# EndEffector.net
KiCad netlist of a schematic drawn in EAGLE
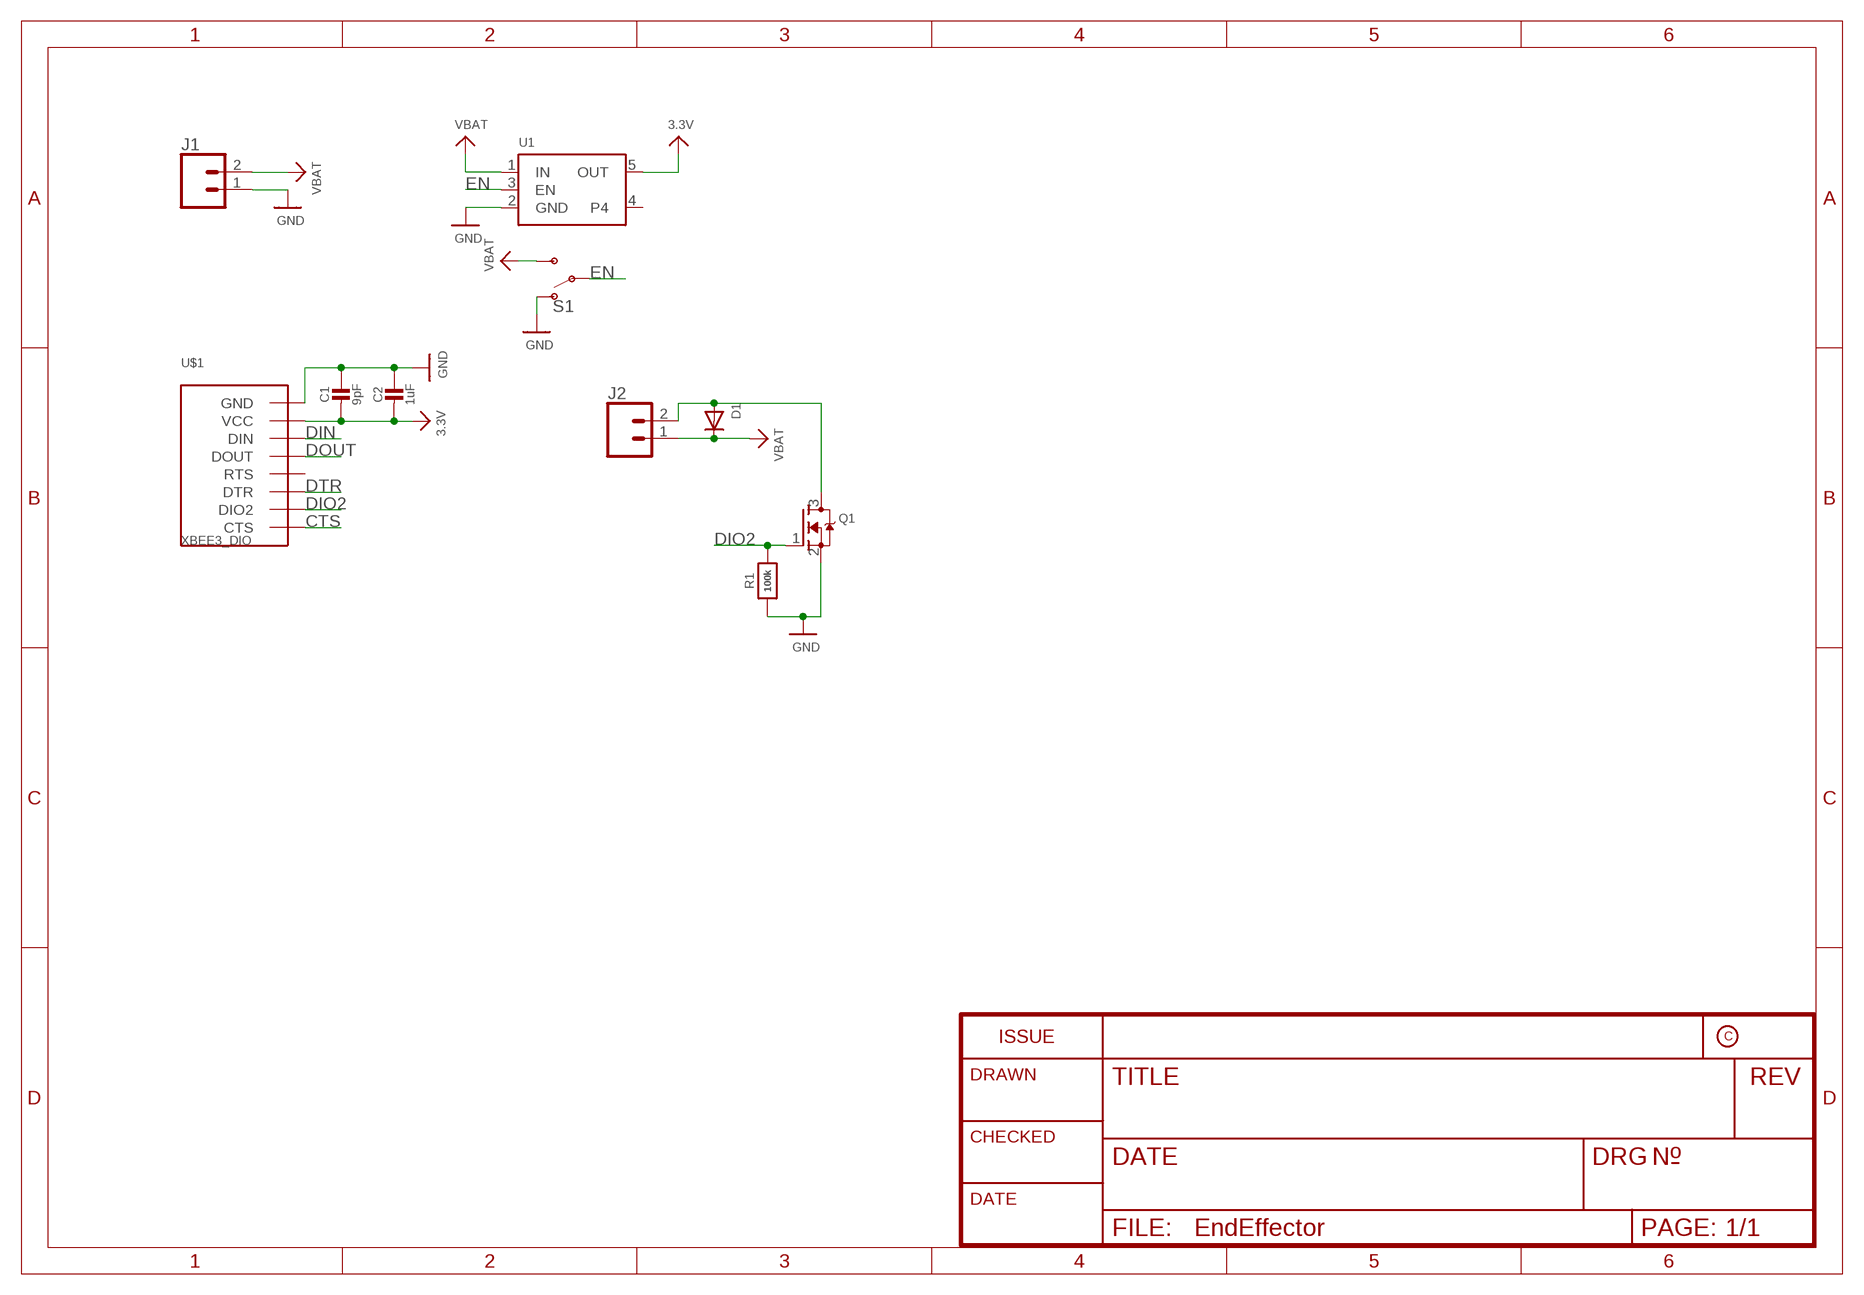
[diagram p0: schematic, sheet 1]

(export (version "E")
  (design (tool "Eeschema 10.0.6"))
  (components
    (comp (ref "C1")
      (value "9pF")
      (footprint "eagle-import:_0603")
      (libsource (lib "eagle-import") (part "CAP_CERAMIC_0603"))
    )
    (comp (ref "C2")
      (value "1uF")
      (footprint "eagle-import:_0603")
      (libsource (lib "eagle-import") (part "CAP_CERAMIC_0603"))
    )
    (comp (ref "D1")
      (value "DIODESOD-123")
      (footprint "eagle-import:SOD-123")
      (libsource (lib "eagle-import") (part "DIODESOD-123"))
    )
    (comp (ref "J1")
      (value "CONN_02")
      (footprint "eagle-import:1X02")
      (libsource (lib "eagle-import") (part "CONN_02"))
    )
    (comp (ref "J2")
      (value "CONN_02")
      (footprint "eagle-import:1X02")
      (libsource (lib "eagle-import") (part "CONN_02"))
    )
    (comp (ref "Q1")
      (value "MOSFET-NREFLOW")
      (footprint "eagle-import:SOT23")
      (libsource (lib "eagle-import") (part "MOSFET-NREFLOW"))
    )
    (comp (ref "R1")
      (value "100k")
      (footprint "eagle-import:_0603")
      (libsource (lib "eagle-import") (part "RESISTOR_0603"))
    )
    (comp (ref "S1")
      (value "SWITCH-SPDT-SMD-RIGHT-ANGLE")
      (footprint "eagle-import:SWITCH_SPST_SMD_A")
      (libsource (lib "eagle-import") (part "SWITCH-SPDT-SMD-RIGHT-ANGLE"))
    )
    (comp (ref "U$1")
      (value "XBEE3_DIO")
      (footprint "eagle-import:XBEE3_MICRO")
      (libsource (lib "eagle-import") (part "XBEE3_DIO"))
    )
    (comp (ref "U1")
      (value "VREG_SOT23-5")
      (footprint "eagle-import:SOT23-5")
      (libsource (lib "eagle-import") (part "VREG_SOT23-5"))
    )
  )
  (nets
    (net (code "1") (name "/CTS") (class "Default")
      (node (ref "U$1") (pin "CTS/DIO7") (pinfunction "CTS_CTS/DIO7") (pintype "bidirectional"))
    )
    (net (code "2") (name "/DIN") (class "Default")
      (node (ref "U$1") (pin "DIN/CONFIG/DIO14") (pinfunction "DIN_DIN/CONFIG/DIO14") (pintype "bidirectional"))
    )
    (net (code "3") (name "/DIO2") (class "Default")
      (node (ref "Q1") (pin "1") (pinfunction "G_1") (pintype "bidirectional"))
      (node (ref "R1") (pin "2") (pinfunction "2_2") (pintype "passive"))
      (node (ref "U$1") (pin "AD2/DIO2") (pinfunction "DIO2_AD2/DIO2") (pintype "bidirectional"))
    )
    (net (code "4") (name "/DOUT") (class "Default")
      (node (ref "U$1") (pin "DOUT/DIO13") (pinfunction "DOUT_DOUT/DIO13") (pintype "bidirectional"))
    )
    (net (code "5") (name "/DTR") (class "Default")
      (node (ref "U$1") (pin "DTR/SLEEP_RQ/DIO8") (pinfunction "DTR_DTR/SLEEP_RQ/DIO8") (pintype "bidirectional"))
    )
    (net (code "6") (name "/EN") (class "Default")
      (node (ref "S1") (pin "2") (pinfunction "P_2") (pintype "passive"))
      (node (ref "U1") (pin "3") (pinfunction "EN_3") (pintype "input"))
    )
    (net (code "7") (name "3.3V") (class "Default")
      (node (ref "C1") (pin "2") (pinfunction "2_2") (pintype "passive"))
      (node (ref "C2") (pin "2") (pinfunction "2_2") (pintype "passive"))
      (node (ref "U$1") (pin "VCC") (pinfunction "VCC_VCC") (pintype "bidirectional"))
      (node (ref "U1") (pin "5") (pinfunction "OUT_5") (pintype "power_in"))
    )
    (net (code "8") (name "GND") (class "Default")
      (node (ref "C1") (pin "1") (pinfunction "1_1") (pintype "passive"))
      (node (ref "C2") (pin "1") (pinfunction "1_1") (pintype "passive"))
      (node (ref "J1") (pin "1") (pinfunction "1_1") (pintype "passive"))
      (node (ref "Q1") (pin "2") (pinfunction "S_2") (pintype "bidirectional"))
      (node (ref "R1") (pin "1") (pinfunction "1_1") (pintype "passive"))
      (node (ref "S1") (pin "1") (pinfunction "O_1") (pintype "passive"))
      (node (ref "U$1") (pin "GND1") (pinfunction "GND_GND1") (pintype "bidirectional"))
      (node (ref "U$1") (pin "GND2") (pinfunction "GND_GND2") (pintype "bidirectional"))
      (node (ref "U$1") (pin "GND3") (pinfunction "GND_GND3") (pintype "bidirectional"))
      (node (ref "U$1") (pin "GND4") (pinfunction "GND_GND4") (pintype "bidirectional"))
      (node (ref "U$1") (pin "GND5") (pinfunction "GND_GND5") (pintype "bidirectional"))
      (node (ref "U$1") (pin "GND6") (pinfunction "GND_GND6") (pintype "bidirectional"))
      (node (ref "U1") (pin "2") (pinfunction "GND_2") (pintype "power_in"))
    )
    (net (code "9") (name "Net-(Q1-D)") (class "Default")
      (node (ref "D1") (pin "A") (pinfunction "A_A") (pintype "passive"))
      (node (ref "J2") (pin "2") (pinfunction "2_2") (pintype "passive"))
      (node (ref "Q1") (pin "3") (pinfunction "D_3") (pintype "bidirectional"))
    )
    (net (code "10") (name "VBAT") (class "Default")
      (node (ref "D1") (pin "C") (pinfunction "C_C") (pintype "passive"))
      (node (ref "J1") (pin "2") (pinfunction "2_2") (pintype "passive"))
      (node (ref "J2") (pin "1") (pinfunction "1_1") (pintype "passive"))
      (node (ref "S1") (pin "3") (pinfunction "S_3") (pintype "passive"))
      (node (ref "U1") (pin "1") (pinfunction "IN_1") (pintype "power_in"))
    )
    (net (code "11") (name "unconnected-(U$1-RTS-PadRTS{slash}DIO6)") (class "Default")
      (node (ref "U$1") (pin "RTS/DIO6") (pinfunction "RTS_RTS/DIO6") (pintype "bidirectional"))
    )
    (net (code "12") (name "unconnected-(U1-P4-Pad4)") (class "Default")
      (node (ref "U1") (pin "4") (pinfunction "P4_4") (pintype "bidirectional"))
    )
  )
)
